# remotecontroll.net
KiCad netlist of a schematic drawn in EAGLE
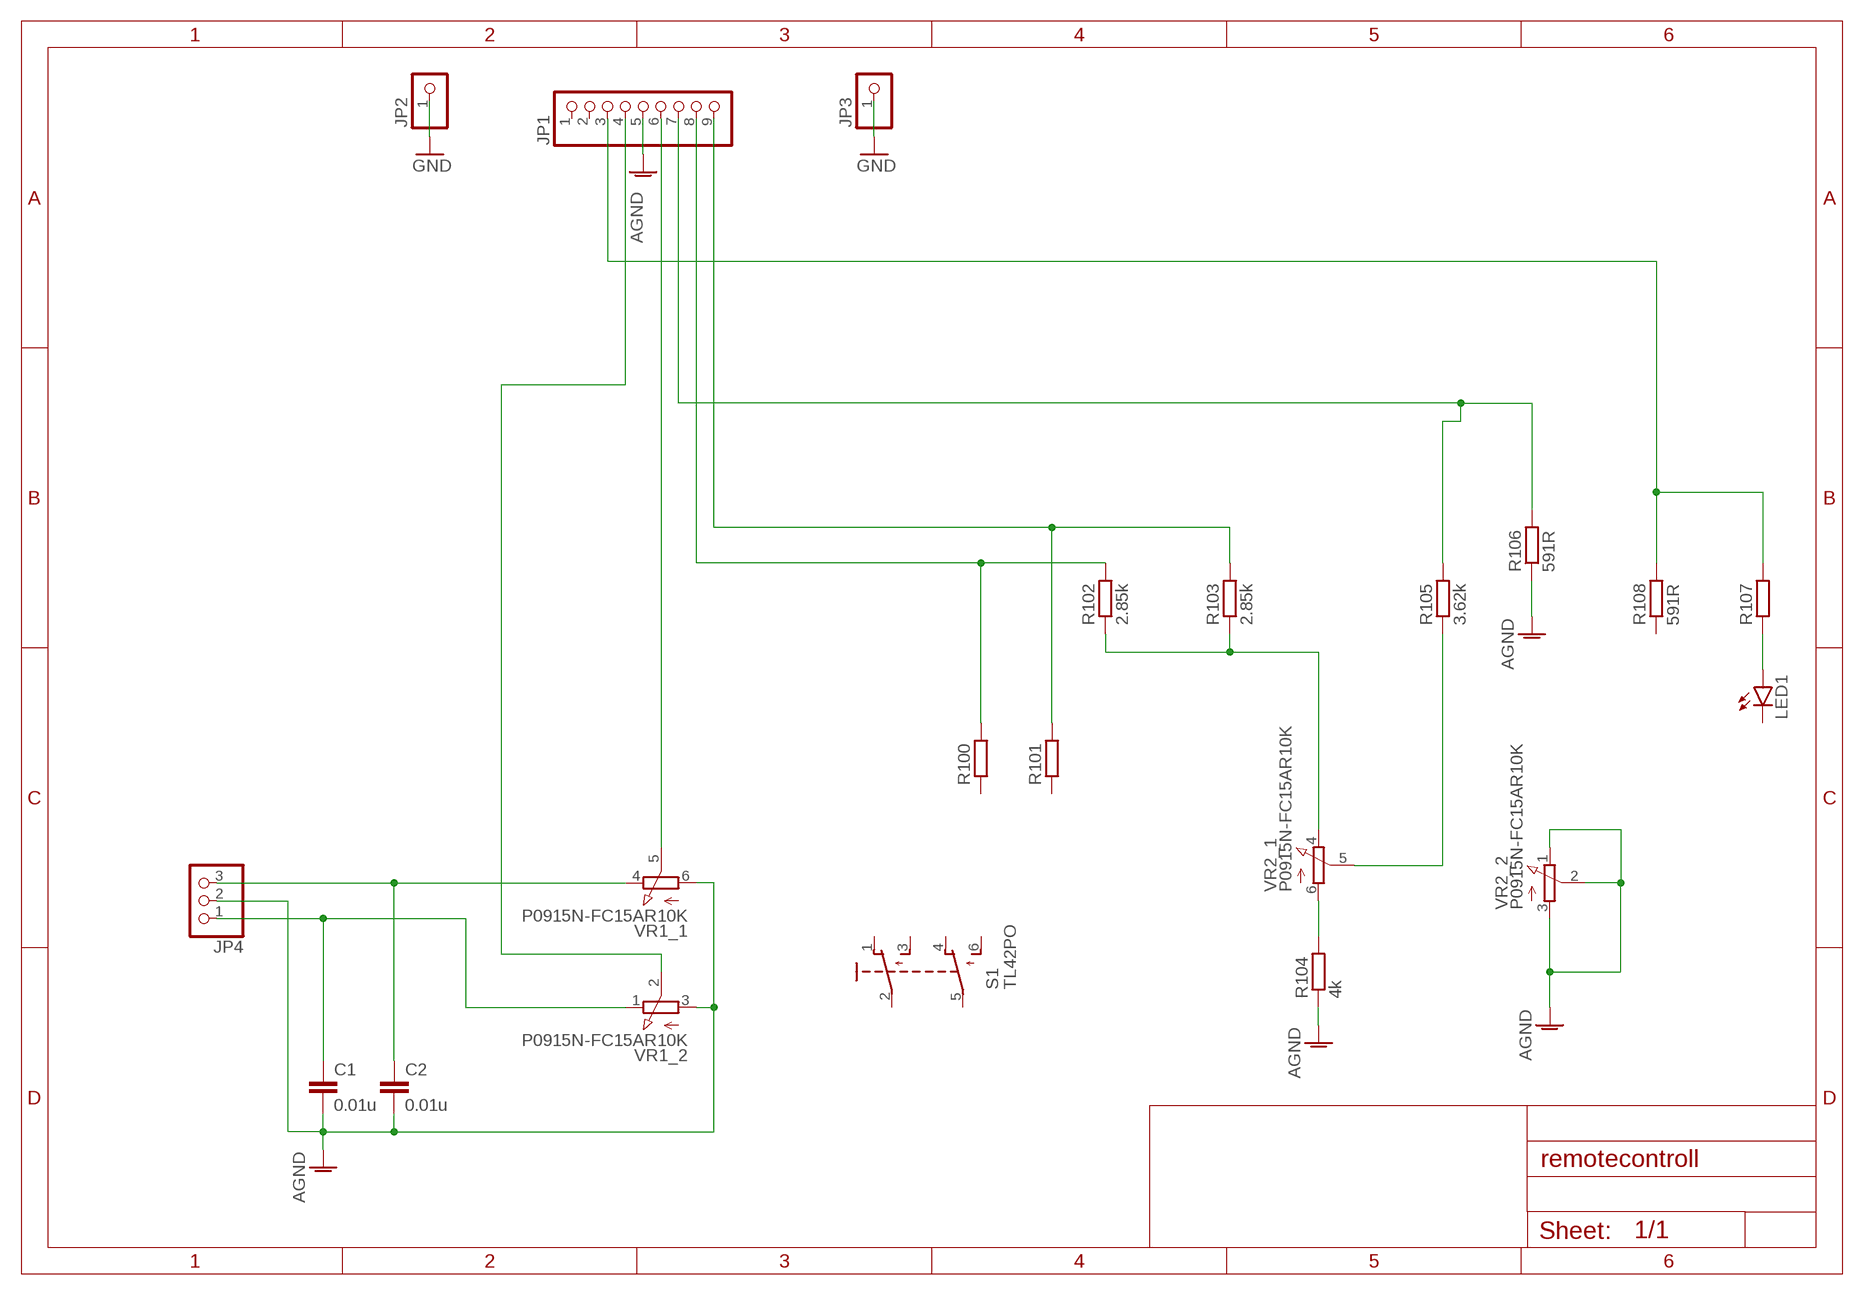
[diagram p0: schematic, sheet 1]

(export (version "E")
  (design (tool "Eeschema 10.0.6"))
  (components
    (comp (ref "C1")
      (value "0.01u")
      (footprint "eagle-import:C0603")
      (libsource (lib "eagle-import") (part "C-EUC0603"))
    )
    (comp (ref "C2")
      (value "0.01u")
      (footprint "eagle-import:C0603")
      (libsource (lib "eagle-import") (part "C-EUC0603"))
    )
    (comp (ref "JP1")
      (value "PINHD-1X9")
      (footprint "eagle-import:1X09")
      (libsource (lib "eagle-import") (part "PINHD-1X9"))
    )
    (comp (ref "JP2")
      (value "PINHD-1X1")
      (footprint "eagle-import:1X01")
      (libsource (lib "eagle-import") (part "PINHD-1X1"))
    )
    (comp (ref "JP3")
      (value "PINHD-1X1")
      (footprint "eagle-import:1X01")
      (libsource (lib "eagle-import") (part "PINHD-1X1"))
    )
    (comp (ref "JP4")
      (value "PINHD-1X3")
      (footprint "eagle-import:1X03")
      (libsource (lib "eagle-import") (part "PINHD-1X3"))
    )
    (comp (ref "LED1")
      (value "LED3MM")
      (footprint "eagle-import:LED3MM")
      (libsource (lib "eagle-import") (part "LED3MM"))
    )
    (comp (ref "R100")
      (value "R-EU_0207/10")
      (footprint "eagle-import:0207_10")
      (libsource (lib "eagle-import") (part "R-EU_0207/10"))
    )
    (comp (ref "R101")
      (value "R-EU_0207/10")
      (footprint "eagle-import:0207_10")
      (libsource (lib "eagle-import") (part "R-EU_0207/10"))
    )
    (comp (ref "R102")
      (value "2.85k")
      (footprint "eagle-import:0204_7")
      (libsource (lib "eagle-import") (part "R-EU_0204/7"))
    )
    (comp (ref "R103")
      (value "2.85k")
      (footprint "eagle-import:0204_7")
      (libsource (lib "eagle-import") (part "R-EU_0204/7"))
    )
    (comp (ref "R104")
      (value "4k")
      (footprint "eagle-import:0204_7")
      (libsource (lib "eagle-import") (part "R-EU_0204/7"))
    )
    (comp (ref "R105")
      (value "3.62k")
      (footprint "eagle-import:0204_7")
      (libsource (lib "eagle-import") (part "R-EU_0204/7"))
    )
    (comp (ref "R106")
      (value "591R")
      (footprint "eagle-import:0204_7")
      (libsource (lib "eagle-import") (part "R-EU_0204/7"))
    )
    (comp (ref "R107")
      (value "R-EU_0207/10")
      (footprint "eagle-import:0207_10")
      (libsource (lib "eagle-import") (part "R-EU_0207/10"))
    )
    (comp (ref "R108")
      (value "591R")
      (footprint "eagle-import:0204_7")
      (libsource (lib "eagle-import") (part "R-EU_0204/7"))
    )
    (comp (ref "S1")
      (value "TL42PO")
      (footprint "eagle-import:TL4XPO")
      (libsource (lib "eagle-import") (part "TL42PO"))
    )
    (comp (ref "VR1")
      (value "P0915N-FC15AR10K")
      (footprint "eagle-import:P0915NFC15AR10K")
      (libsource (lib "eagle-import") (part "P0915N-FC15AR10K"))
    )
    (comp (ref "VR2")
      (value "P0915N-FC15AR10K")
      (footprint "eagle-import:P0915NFC15AR10K")
      (libsource (lib "eagle-import") (part "P0915N-FC15AR10K"))
    )
  )
  (nets
    (net (code "1") (name "AGND") (class "Default")
      (node (ref "C1") (pin "2") (pinfunction "2_2") (pintype "passive"))
      (node (ref "C2") (pin "2") (pinfunction "2_2") (pintype "passive"))
      (node (ref "JP1") (pin "5") (pinfunction "5_5") (pintype "passive"))
      (node (ref "JP4") (pin "2") (pinfunction "2_2") (pintype "passive"))
      (node (ref "R104") (pin "1") (pinfunction "1_1") (pintype "passive"))
      (node (ref "R106") (pin "1") (pinfunction "1_1") (pintype "passive"))
      (node (ref "VR1") (pin "3") (pinfunction "A_3") (pintype "passive"))
      (node (ref "VR1") (pin "6") (pinfunction "A_6") (pintype "passive"))
      (node (ref "VR2") (pin "1") (pinfunction "E_1") (pintype "passive"))
      (node (ref "VR2") (pin "2") (pinfunction "S_2") (pintype "passive"))
      (node (ref "VR2") (pin "3") (pinfunction "A_3") (pintype "passive"))
    )
    (net (code "2") (name "GND") (class "Default")
      (node (ref "JP2") (pin "1") (pinfunction "1_1") (pintype "passive"))
      (node (ref "JP3") (pin "1") (pinfunction "1_1") (pintype "passive"))
    )
    (net (code "3") (name "Net-(JP1-Pad3)") (class "Default")
      (node (ref "JP1") (pin "3") (pinfunction "3_3") (pintype "passive"))
      (node (ref "R107") (pin "2") (pinfunction "2_2") (pintype "passive"))
      (node (ref "R108") (pin "2") (pinfunction "2_2") (pintype "passive"))
    )
    (net (code "4") (name "Net-(JP1-Pad7)") (class "Default")
      (node (ref "JP1") (pin "7") (pinfunction "7_7") (pintype "passive"))
      (node (ref "R105") (pin "2") (pinfunction "2_2") (pintype "passive"))
      (node (ref "R106") (pin "2") (pinfunction "2_2") (pintype "passive"))
    )
    (net (code "5") (name "Net-(JP1-Pad8)") (class "Default")
      (node (ref "JP1") (pin "8") (pinfunction "8_8") (pintype "passive"))
      (node (ref "R100") (pin "2") (pinfunction "2_2") (pintype "passive"))
      (node (ref "R102") (pin "2") (pinfunction "2_2") (pintype "passive"))
    )
    (net (code "6") (name "Net-(JP1-Pad9)") (class "Default")
      (node (ref "JP1") (pin "9") (pinfunction "9_9") (pintype "passive"))
      (node (ref "R101") (pin "2") (pinfunction "2_2") (pintype "passive"))
      (node (ref "R103") (pin "2") (pinfunction "2_2") (pintype "passive"))
    )
    (net (code "7") (name "Net-(LED1-PadA)") (class "Default")
      (node (ref "LED1") (pin "A") (pinfunction "A_A") (pintype "passive"))
      (node (ref "R107") (pin "1") (pinfunction "1_1") (pintype "passive"))
    )
    (net (code "8") (name "Net-(VR1A-E)") (class "Default")
      (node (ref "C2") (pin "1") (pinfunction "1_1") (pintype "passive"))
      (node (ref "JP4") (pin "3") (pinfunction "3_3") (pintype "passive"))
      (node (ref "VR1") (pin "4") (pinfunction "E_4") (pintype "passive"))
    )
    (net (code "9") (name "Net-(VR1A-S)") (class "Default")
      (node (ref "JP1") (pin "6") (pinfunction "6_6") (pintype "passive"))
      (node (ref "VR1") (pin "5") (pinfunction "S_5") (pintype "passive"))
    )
    (net (code "10") (name "Net-(VR1B-E)") (class "Default")
      (node (ref "C1") (pin "1") (pinfunction "1_1") (pintype "passive"))
      (node (ref "JP4") (pin "1") (pinfunction "1_1") (pintype "passive"))
      (node (ref "VR1") (pin "1") (pinfunction "E_1") (pintype "passive"))
    )
    (net (code "11") (name "Net-(VR1B-S)") (class "Default")
      (node (ref "JP1") (pin "4") (pinfunction "4_4") (pintype "passive"))
      (node (ref "VR1") (pin "2") (pinfunction "S_2") (pintype "passive"))
    )
    (net (code "12") (name "Net-(VR2A-A)") (class "Default")
      (node (ref "R104") (pin "2") (pinfunction "2_2") (pintype "passive"))
      (node (ref "VR2") (pin "6") (pinfunction "A_6") (pintype "passive"))
    )
    (net (code "13") (name "Net-(VR2A-E)") (class "Default")
      (node (ref "R102") (pin "1") (pinfunction "1_1") (pintype "passive"))
      (node (ref "R103") (pin "1") (pinfunction "1_1") (pintype "passive"))
      (node (ref "VR2") (pin "4") (pinfunction "E_4") (pintype "passive"))
    )
    (net (code "14") (name "Net-(VR2A-S)") (class "Default")
      (node (ref "R105") (pin "1") (pinfunction "1_1") (pintype "passive"))
      (node (ref "VR2") (pin "5") (pinfunction "S_5") (pintype "passive"))
    )
    (net (code "15") (name "unconnected-(JP1-Pad1)") (class "Default")
      (node (ref "JP1") (pin "1") (pinfunction "1_1") (pintype "passive"))
    )
    (net (code "16") (name "unconnected-(JP1-Pad2)") (class "Default")
      (node (ref "JP1") (pin "2") (pinfunction "2_2") (pintype "passive"))
    )
    (net (code "17") (name "unconnected-(LED1-C-PadK)") (class "Default")
      (node (ref "LED1") (pin "K") (pinfunction "C_K") (pintype "passive"))
    )
    (net (code "18") (name "unconnected-(R100-Pad1)") (class "Default")
      (node (ref "R100") (pin "1") (pinfunction "1_1") (pintype "passive"))
    )
    (net (code "19") (name "unconnected-(R101-Pad1)") (class "Default")
      (node (ref "R101") (pin "1") (pinfunction "1_1") (pintype "passive"))
    )
    (net (code "20") (name "unconnected-(R108-Pad1)") (class "Default")
      (node (ref "R108") (pin "1") (pinfunction "1_1") (pintype "passive"))
    )
    (net (code "21") (name "unconnected-(S1-O-Pad1)") (class "Default")
      (node (ref "S1") (pin "1") (pinfunction "O_1") (pintype "passive"))
    )
    (net (code "22") (name "unconnected-(S1-O1-Pad4)") (class "Default")
      (node (ref "S1") (pin "4") (pinfunction "O1_4") (pintype "passive"))
    )
    (net (code "23") (name "unconnected-(S1-P-Pad2)") (class "Default")
      (node (ref "S1") (pin "2") (pinfunction "P_2") (pintype "passive"))
    )
    (net (code "24") (name "unconnected-(S1-P1-Pad5)") (class "Default")
      (node (ref "S1") (pin "5") (pinfunction "P1_5") (pintype "passive"))
    )
    (net (code "25") (name "unconnected-(S1-S-Pad3)") (class "Default")
      (node (ref "S1") (pin "3") (pinfunction "S_3") (pintype "passive"))
    )
    (net (code "26") (name "unconnected-(S1-S1-Pad6)") (class "Default")
      (node (ref "S1") (pin "6") (pinfunction "S1_6") (pintype "passive"))
    )
  )
)
